# PCI_short_card_universal_-_32_BIT-3.net
KiCad netlist of a schematic drawn in Altium Designer
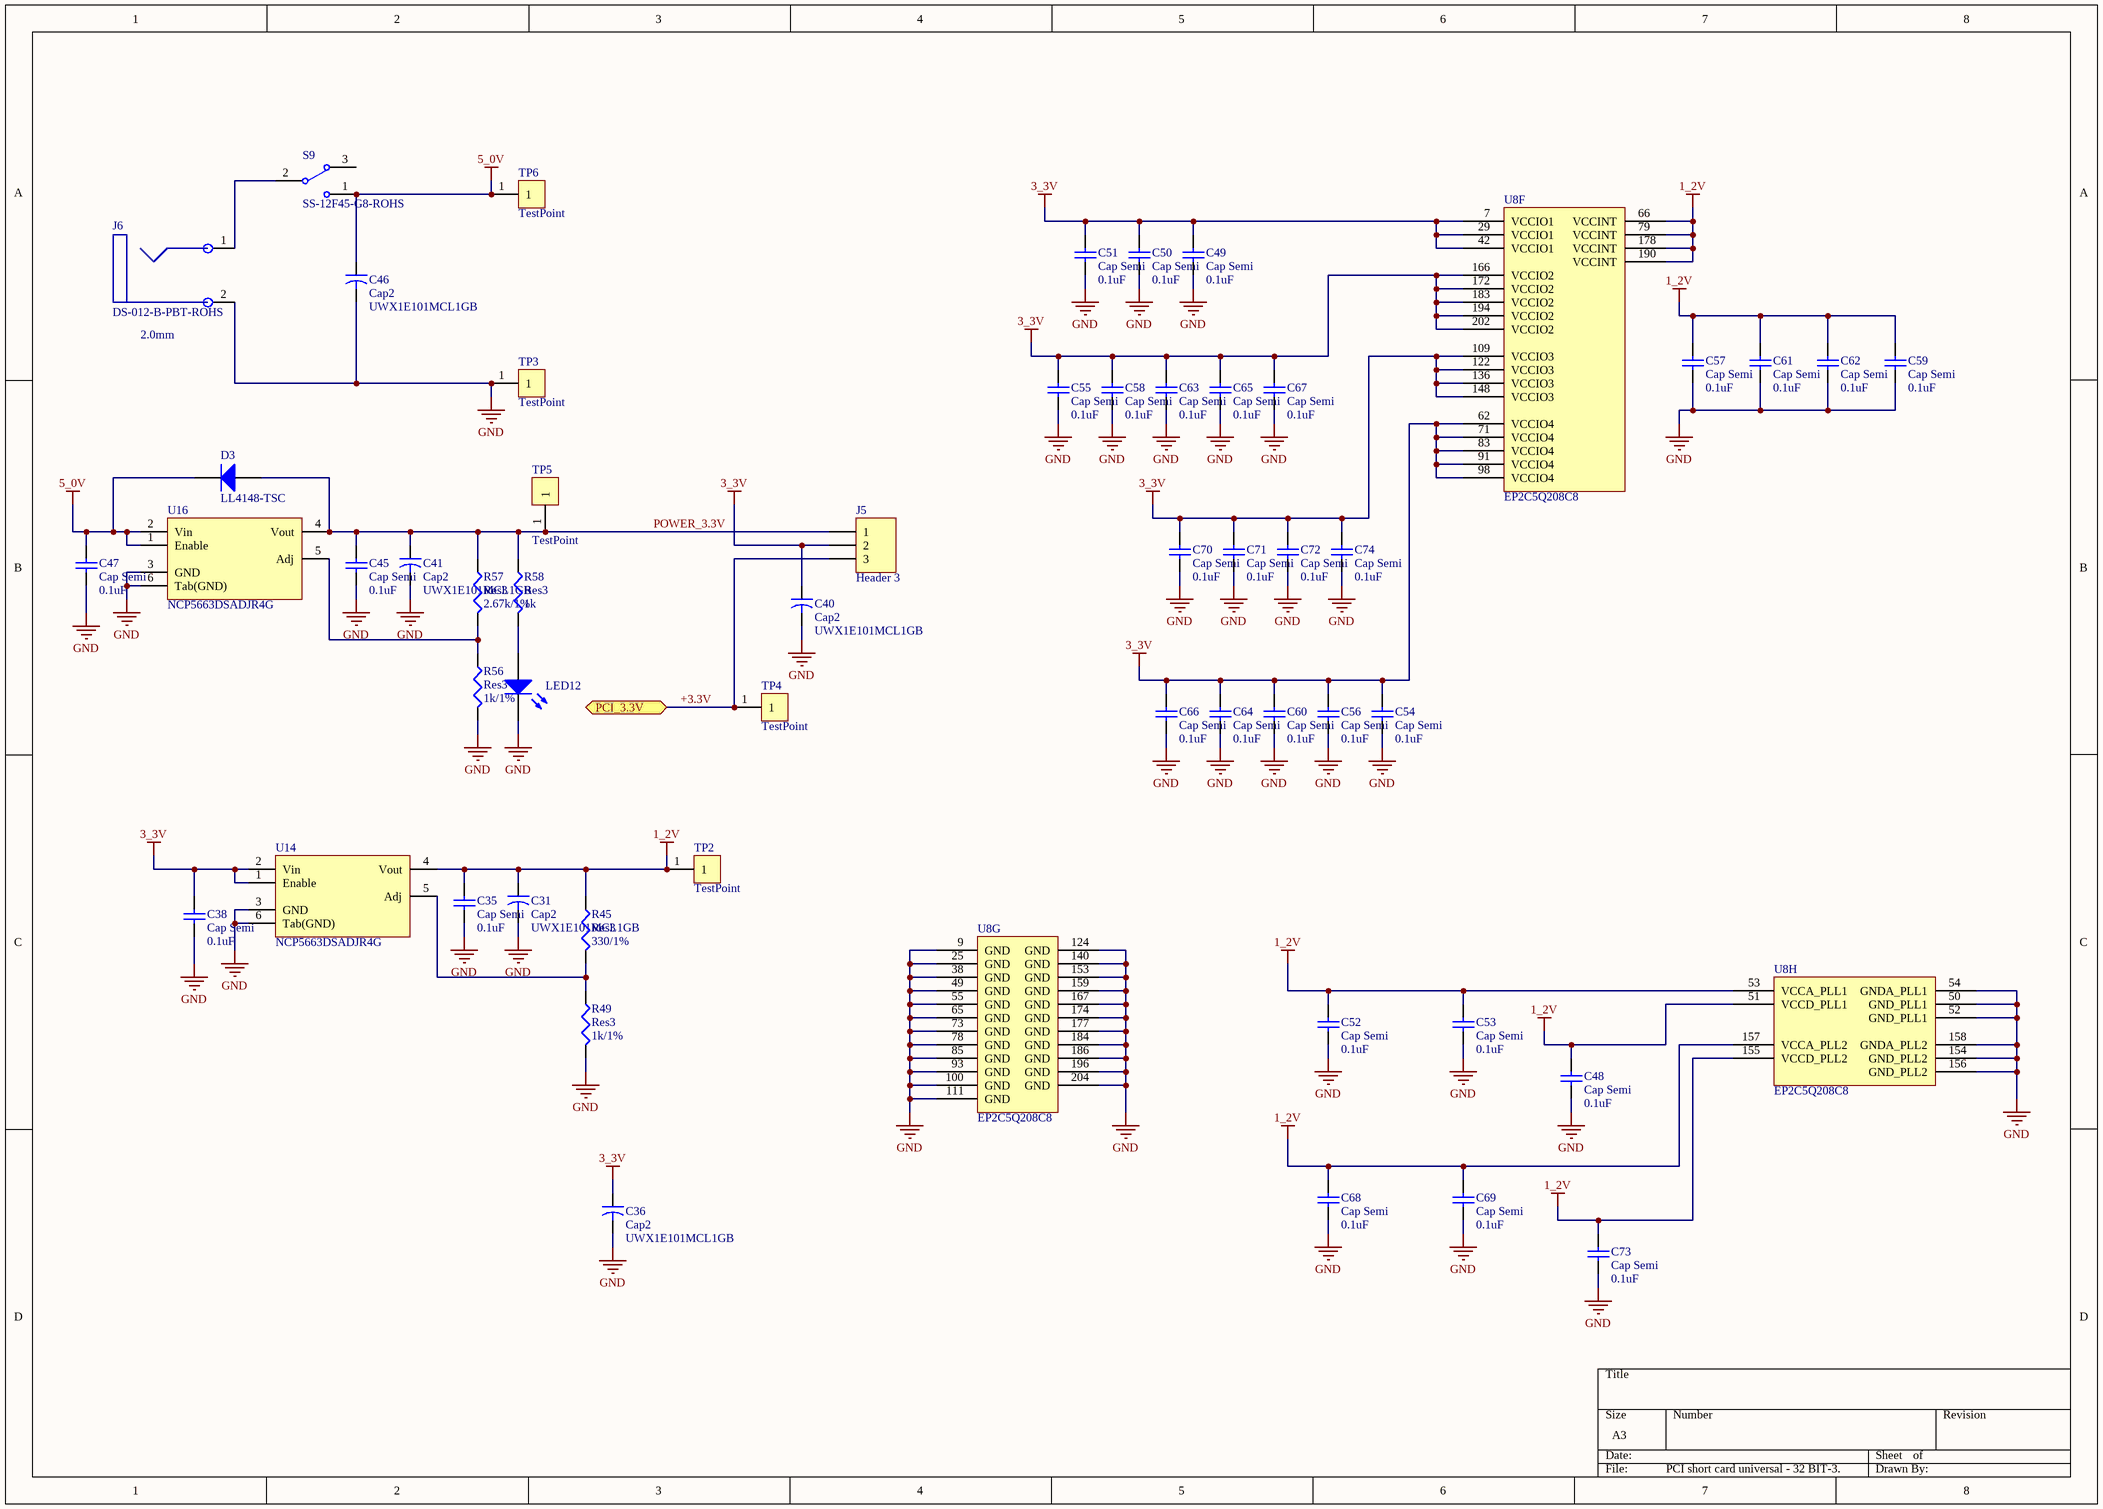
[diagram p0: PCI short card universal - 32 BIT-3.schdoc]

(export (version "E")
  (design (tool "Eeschema 10.0.6"))
  (components
    (comp (ref "C31")
      (value "Cap2")
      (footprint "ECEL_D8")
      (description "NICHICON")
      (fields (field (name "ALTIUM_VALUE") "UWX1E101MCL1GB") (field (name "PUBLISHER") "Altium Limited"))
      (libsource (lib "Miscellaneous Devices") (part "Cap2"))
    )
    (comp (ref "C35")
      (value "Cap Semi")
      (footprint "RESC1608N")
      (description "Capacitor (Semiconductor SIM Model)")
      (fields (field (name "ALTIUM_VALUE") "0.1uF") (field (name "PUBLISHER") "Altium Limited"))
      (libsource (lib "Miscellaneous Devices") (part "Cap Semi"))
    )
    (comp (ref "C36")
      (value "Cap2")
      (footprint "ECEL_D8")
      (description "NICHICON")
      (fields (field (name "ALTIUM_VALUE") "UWX1E101MCL1GB") (field (name "PUBLISHER") "Altium Limited"))
      (libsource (lib "Miscellaneous Devices") (part "Cap2"))
    )
    (comp (ref "C38")
      (value "Cap Semi")
      (footprint "RESC1608N")
      (description "Capacitor (Semiconductor SIM Model)")
      (fields (field (name "ALTIUM_VALUE") "0.1uF") (field (name "PUBLISHER") "Altium Limited"))
      (libsource (lib "Miscellaneous Devices") (part "Cap Semi"))
    )
    (comp (ref "C40")
      (value "Cap2")
      (footprint "ECEL_D8")
      (description "NICHICON")
      (fields (field (name "ALTIUM_VALUE") "UWX1E101MCL1GB") (field (name "PUBLISHER") "Altium Limited"))
      (libsource (lib "Miscellaneous Devices") (part "Cap2"))
    )
    (comp (ref "C41")
      (value "Cap2")
      (footprint "ECEL_D8")
      (description "NICHICON")
      (fields (field (name "ALTIUM_VALUE") "UWX1E101MCL1GB") (field (name "PUBLISHER") "Altium Limited"))
      (libsource (lib "Miscellaneous Devices") (part "Cap2"))
    )
    (comp (ref "C45")
      (value "Cap Semi")
      (footprint "RESC1608N")
      (description "Capacitor (Semiconductor SIM Model)")
      (fields (field (name "ALTIUM_VALUE") "0.1uF") (field (name "PUBLISHER") "Altium Limited"))
      (libsource (lib "Miscellaneous Devices") (part "Cap Semi"))
    )
    (comp (ref "C46")
      (value "Cap2")
      (footprint "ECEL_D8")
      (description "NICHICON")
      (fields (field (name "ALTIUM_VALUE") "UWX1E101MCL1GB") (field (name "PUBLISHER") "Altium Limited"))
      (libsource (lib "Miscellaneous Devices") (part "Cap2"))
    )
    (comp (ref "C47")
      (value "Cap Semi")
      (footprint "RESC1608N")
      (description "Capacitor (Semiconductor SIM Model)")
      (fields (field (name "ALTIUM_VALUE") "0.1uF") (field (name "PUBLISHER") "Altium Limited"))
      (libsource (lib "Miscellaneous Devices") (part "Cap Semi"))
    )
    (comp (ref "C48")
      (value "Cap Semi")
      (footprint "RESC1608N")
      (description "Capacitor (Semiconductor SIM Model)")
      (fields (field (name "ALTIUM_VALUE") "0.1uF") (field (name "PUBLISHER") "Altium Limited"))
      (libsource (lib "Miscellaneous Devices") (part "Cap Semi"))
    )
    (comp (ref "C49")
      (value "Cap Semi")
      (footprint "RESC1608N")
      (description "Capacitor (Semiconductor SIM Model)")
      (fields (field (name "ALTIUM_VALUE") "0.1uF") (field (name "PUBLISHER") "Altium Limited"))
      (libsource (lib "Miscellaneous Devices") (part "Cap Semi"))
    )
    (comp (ref "C50")
      (value "Cap Semi")
      (footprint "RESC1608N")
      (description "Capacitor (Semiconductor SIM Model)")
      (fields (field (name "ALTIUM_VALUE") "0.1uF") (field (name "PUBLISHER") "Altium Limited"))
      (libsource (lib "Miscellaneous Devices") (part "Cap Semi"))
    )
    (comp (ref "C51")
      (value "Cap Semi")
      (footprint "RESC1608N")
      (description "Capacitor (Semiconductor SIM Model)")
      (fields (field (name "ALTIUM_VALUE") "0.1uF") (field (name "PUBLISHER") "Altium Limited"))
      (libsource (lib "Miscellaneous Devices") (part "Cap Semi"))
    )
    (comp (ref "C52")
      (value "Cap Semi")
      (footprint "RESC1608N")
      (description "Capacitor (Semiconductor SIM Model)")
      (fields (field (name "ALTIUM_VALUE") "0.1uF") (field (name "PUBLISHER") "Altium Limited"))
      (libsource (lib "Miscellaneous Devices") (part "Cap Semi"))
    )
    (comp (ref "C53")
      (value "Cap Semi")
      (footprint "RESC1608N")
      (description "Capacitor (Semiconductor SIM Model)")
      (fields (field (name "ALTIUM_VALUE") "0.1uF") (field (name "PUBLISHER") "Altium Limited"))
      (libsource (lib "Miscellaneous Devices") (part "Cap Semi"))
    )
    (comp (ref "C54")
      (value "Cap Semi")
      (footprint "RESC1608N")
      (description "Capacitor (Semiconductor SIM Model)")
      (fields (field (name "ALTIUM_VALUE") "0.1uF") (field (name "PUBLISHER") "Altium Limited"))
      (libsource (lib "Miscellaneous Devices") (part "Cap Semi"))
    )
    (comp (ref "C55")
      (value "Cap Semi")
      (footprint "RESC1608N")
      (description "Capacitor (Semiconductor SIM Model)")
      (fields (field (name "ALTIUM_VALUE") "0.1uF") (field (name "PUBLISHER") "Altium Limited"))
      (libsource (lib "Miscellaneous Devices") (part "Cap Semi"))
    )
    (comp (ref "C56")
      (value "Cap Semi")
      (footprint "RESC1608N")
      (description "Capacitor (Semiconductor SIM Model)")
      (fields (field (name "ALTIUM_VALUE") "0.1uF") (field (name "PUBLISHER") "Altium Limited"))
      (libsource (lib "Miscellaneous Devices") (part "Cap Semi"))
    )
    (comp (ref "C57")
      (value "Cap Semi")
      (footprint "RESC1608N")
      (description "Capacitor (Semiconductor SIM Model)")
      (fields (field (name "ALTIUM_VALUE") "0.1uF") (field (name "PUBLISHER") "Altium Limited"))
      (libsource (lib "Miscellaneous Devices") (part "Cap Semi"))
    )
    (comp (ref "C58")
      (value "Cap Semi")
      (footprint "RESC1608N")
      (description "Capacitor (Semiconductor SIM Model)")
      (fields (field (name "ALTIUM_VALUE") "0.1uF") (field (name "PUBLISHER") "Altium Limited"))
      (libsource (lib "Miscellaneous Devices") (part "Cap Semi"))
    )
    (comp (ref "C59")
      (value "Cap Semi")
      (footprint "RESC1608N")
      (description "Capacitor (Semiconductor SIM Model)")
      (fields (field (name "ALTIUM_VALUE") "0.1uF") (field (name "PUBLISHER") "Altium Limited"))
      (libsource (lib "Miscellaneous Devices") (part "Cap Semi"))
    )
    (comp (ref "C60")
      (value "Cap Semi")
      (footprint "RESC1608N")
      (description "Capacitor (Semiconductor SIM Model)")
      (fields (field (name "ALTIUM_VALUE") "0.1uF") (field (name "PUBLISHER") "Altium Limited"))
      (libsource (lib "Miscellaneous Devices") (part "Cap Semi"))
    )
    (comp (ref "C61")
      (value "Cap Semi")
      (footprint "RESC1608N")
      (description "Capacitor (Semiconductor SIM Model)")
      (fields (field (name "ALTIUM_VALUE") "0.1uF") (field (name "PUBLISHER") "Altium Limited"))
      (libsource (lib "Miscellaneous Devices") (part "Cap Semi"))
    )
    (comp (ref "C62")
      (value "Cap Semi")
      (footprint "RESC1608N")
      (description "Capacitor (Semiconductor SIM Model)")
      (fields (field (name "ALTIUM_VALUE") "0.1uF") (field (name "PUBLISHER") "Altium Limited"))
      (libsource (lib "Miscellaneous Devices") (part "Cap Semi"))
    )
    (comp (ref "C63")
      (value "Cap Semi")
      (footprint "RESC1608N")
      (description "Capacitor (Semiconductor SIM Model)")
      (fields (field (name "ALTIUM_VALUE") "0.1uF") (field (name "PUBLISHER") "Altium Limited"))
      (libsource (lib "Miscellaneous Devices") (part "Cap Semi"))
    )
    (comp (ref "C64")
      (value "Cap Semi")
      (footprint "RESC1608N")
      (description "Capacitor (Semiconductor SIM Model)")
      (fields (field (name "ALTIUM_VALUE") "0.1uF") (field (name "PUBLISHER") "Altium Limited"))
      (libsource (lib "Miscellaneous Devices") (part "Cap Semi"))
    )
    (comp (ref "C65")
      (value "Cap Semi")
      (footprint "RESC1608N")
      (description "Capacitor (Semiconductor SIM Model)")
      (fields (field (name "ALTIUM_VALUE") "0.1uF") (field (name "PUBLISHER") "Altium Limited"))
      (libsource (lib "Miscellaneous Devices") (part "Cap Semi"))
    )
    (comp (ref "C66")
      (value "Cap Semi")
      (footprint "RESC1608N")
      (description "Capacitor (Semiconductor SIM Model)")
      (fields (field (name "ALTIUM_VALUE") "0.1uF") (field (name "PUBLISHER") "Altium Limited"))
      (libsource (lib "Miscellaneous Devices") (part "Cap Semi"))
    )
    (comp (ref "C67")
      (value "Cap Semi")
      (footprint "RESC1608N")
      (description "Capacitor (Semiconductor SIM Model)")
      (fields (field (name "ALTIUM_VALUE") "0.1uF") (field (name "PUBLISHER") "Altium Limited"))
      (libsource (lib "Miscellaneous Devices") (part "Cap Semi"))
    )
    (comp (ref "C68")
      (value "Cap Semi")
      (footprint "RESC1608N")
      (description "Capacitor (Semiconductor SIM Model)")
      (fields (field (name "ALTIUM_VALUE") "0.1uF") (field (name "PUBLISHER") "Altium Limited"))
      (libsource (lib "Miscellaneous Devices") (part "Cap Semi"))
    )
    (comp (ref "C69")
      (value "Cap Semi")
      (footprint "RESC1608N")
      (description "Capacitor (Semiconductor SIM Model)")
      (fields (field (name "ALTIUM_VALUE") "0.1uF") (field (name "PUBLISHER") "Altium Limited"))
      (libsource (lib "Miscellaneous Devices") (part "Cap Semi"))
    )
    (comp (ref "C70")
      (value "Cap Semi")
      (footprint "RESC1608N")
      (description "Capacitor (Semiconductor SIM Model)")
      (fields (field (name "ALTIUM_VALUE") "0.1uF") (field (name "PUBLISHER") "Altium Limited"))
      (libsource (lib "Miscellaneous Devices") (part "Cap Semi"))
    )
    (comp (ref "C71")
      (value "Cap Semi")
      (footprint "RESC1608N")
      (description "Capacitor (Semiconductor SIM Model)")
      (fields (field (name "ALTIUM_VALUE") "0.1uF") (field (name "PUBLISHER") "Altium Limited"))
      (libsource (lib "Miscellaneous Devices") (part "Cap Semi"))
    )
    (comp (ref "C72")
      (value "Cap Semi")
      (footprint "RESC1608N")
      (description "Capacitor (Semiconductor SIM Model)")
      (fields (field (name "ALTIUM_VALUE") "0.1uF") (field (name "PUBLISHER") "Altium Limited"))
      (libsource (lib "Miscellaneous Devices") (part "Cap Semi"))
    )
    (comp (ref "C73")
      (value "Cap Semi")
      (footprint "RESC1608N")
      (description "Capacitor (Semiconductor SIM Model)")
      (fields (field (name "ALTIUM_VALUE") "0.1uF") (field (name "PUBLISHER") "Altium Limited"))
      (libsource (lib "Miscellaneous Devices") (part "Cap Semi"))
    )
    (comp (ref "C74")
      (value "Cap Semi")
      (footprint "RESC1608N")
      (description "Capacitor (Semiconductor SIM Model)")
      (fields (field (name "ALTIUM_VALUE") "0.1uF") (field (name "PUBLISHER") "Altium Limited"))
      (libsource (lib "Miscellaneous Devices") (part "Cap Semi"))
    )
    (comp (ref "D3")
      (value "LL4148-TSC")
      (footprint "SOD80C")
      (description "TAIWAN SEMICONDUCTOR")
      (fields (field (name "PUBLISHER") "Altium Limited"))
      (libsource (lib "Philips Discrete Diode - Switching") (part "BAS32L"))
    )
    (comp (ref "J5")
      (value "Header 3")
      (footprint "HDR1X3")
      (description "Header, 3-Pin")
      (fields (field (name "PUBLISHER") "Altium Limited"))
      (libsource (lib "Miscellaneous Connectors") (part "Header 3"))
    )
    (comp (ref "J6")
      (value "DS-012-B-PBT-ROHS")
      (footprint "JACK")
      (description "WEALTH METAL")
      (libsource (lib "Schlib1") (part "JACK2.5mm"))
    )
    (comp (ref "LED12")
      (value "LED2")
      (footprint "LED3.2X1.6X1.1")
      (description "OASISTEK (TO-3216BC-MAE)")
      (fields (field (name "PUBLISHER") "Altium Limited"))
      (libsource (lib "Miscellaneous Devices") (part "LED2"))
    )
    (comp (ref "R45")
      (value "Res3")
      (footprint "RESC1608N")
      (description "Resistor")
      (fields (field (name "ALTIUM_VALUE") "330/1%") (field (name "PUBLISHER") "Altium Limited"))
      (libsource (lib "Miscellaneous Devices") (part "Res3"))
    )
    (comp (ref "R49")
      (value "Res3")
      (footprint "RESC1608N")
      (description "Resistor")
      (fields (field (name "ALTIUM_VALUE") "1k/1%") (field (name "PUBLISHER") "Altium Limited"))
      (libsource (lib "Miscellaneous Devices") (part "Res3"))
    )
    (comp (ref "R56")
      (value "Res3")
      (footprint "RESC1608N")
      (description "Resistor")
      (fields (field (name "ALTIUM_VALUE") "1k/1%") (field (name "PUBLISHER") "Altium Limited"))
      (libsource (lib "Miscellaneous Devices") (part "Res3"))
    )
    (comp (ref "R57")
      (value "Res3")
      (footprint "RESC1608N")
      (description "Resistor")
      (fields (field (name "ALTIUM_VALUE") "2.67k/1%") (field (name "PUBLISHER") "Altium Limited"))
      (libsource (lib "Miscellaneous Devices") (part "Res3"))
    )
    (comp (ref "R58")
      (value "Res3")
      (footprint "RESC1608N")
      (description "Resistor")
      (fields (field (name "ALTIUM_VALUE") "1k") (field (name "PUBLISHER") "Altium Limited"))
      (libsource (lib "Miscellaneous Devices") (part "Res3"))
    )
    (comp (ref "S9")
      (value "SS-12F45-G8-ROHS")
      (footprint "SLIDE_SW_2TYPE")
      (description "WEALTH METAL")
      (fields (field (name "PUBLISHER") "Altium Limited"))
      (libsource (lib "Miscellaneous Devices") (part "SW-SPDT"))
    )
    (comp (ref "TP2") (value "TestPoint") (footprint "HDR1X1") (libsource (lib "Schlib1") (part "TestPoint")))
    (comp (ref "TP3") (value "TestPoint") (footprint "HDR1X1") (libsource (lib "Schlib1") (part "TestPoint")))
    (comp (ref "TP4") (value "TestPoint") (footprint "HDR1X1") (libsource (lib "Schlib1") (part "TestPoint")))
    (comp (ref "TP5") (value "TestPoint") (footprint "HDR1X1") (libsource (lib "") (part "TestPoint_1")))
    (comp (ref "TP6") (value "TestPoint") (footprint "HDR1X1") (libsource (lib "Schlib1") (part "TestPoint")))
    (comp (ref "U8")
      (value "EP2C5Q208C8")
      (footprint "PQFP208_N")
      (fields (field (name "PUBLISHER") "Altium Limited"))
      (libsource (lib "Altera Cyclone II") (part "EP2C5Q208C8"))
    )
    (comp (ref "U14")
      (value "NCP5663DSADJR4G")
      (footprint "D2PAK(936AA)")
      (description "ON SEMI")
      (libsource (lib "Schlib1") (part "NCP5663DSADJR4G"))
    )
    (comp (ref "U16")
      (value "NCP5663DSADJR4G")
      (footprint "D2PAK(936AA)")
      (description "ON SEMI")
      (libsource (lib "Schlib1") (part "NCP5663DSADJR4G"))
    )
  )
  (nets
    (net (code "1") (name "/+3.3V") (class "Default")
      (node (ref "J5") (pin "3") (pinfunction "3_3") (pintype "passive"))
      (node (ref "TP4") (pin "1") (pinfunction "1_1") (pintype "passive"))
    )
    (net (code "2") (name "/POWER_3.3V") (class "Default")
      (node (ref "C41") (pin "1") (pinfunction "1_1") (pintype "passive"))
      (node (ref "C45") (pin "2") (pinfunction "2_2") (pintype "passive"))
      (node (ref "D3") (pin "1") (pinfunction "A_1") (pintype "passive"))
      (node (ref "J5") (pin "1") (pinfunction "1_1") (pintype "passive"))
      (node (ref "R57") (pin "1") (pinfunction "1_1") (pintype "passive"))
      (node (ref "R58") (pin "1") (pinfunction "1_1") (pintype "passive"))
      (node (ref "TP5") (pin "1") (pinfunction "1_1") (pintype "passive"))
      (node (ref "U16") (pin "4") (pinfunction "Vout_4") (pintype "passive"))
    )
    (net (code "3") (name "1_2V") (class "Default")
      (node (ref "C31") (pin "1") (pinfunction "1_1") (pintype "passive"))
      (node (ref "C35") (pin "2") (pinfunction "2_2") (pintype "passive"))
      (node (ref "C48") (pin "2") (pinfunction "2_2") (pintype "passive"))
      (node (ref "C52") (pin "2") (pinfunction "2_2") (pintype "passive"))
      (node (ref "C53") (pin "2") (pinfunction "2_2") (pintype "passive"))
      (node (ref "C57") (pin "2") (pinfunction "2_2") (pintype "passive"))
      (node (ref "C59") (pin "2") (pinfunction "2_2") (pintype "passive"))
      (node (ref "C61") (pin "2") (pinfunction "2_2") (pintype "passive"))
      (node (ref "C62") (pin "2") (pinfunction "2_2") (pintype "passive"))
      (node (ref "C68") (pin "2") (pinfunction "2_2") (pintype "passive"))
      (node (ref "C69") (pin "2") (pinfunction "2_2") (pintype "passive"))
      (node (ref "C73") (pin "2") (pinfunction "2_2") (pintype "passive"))
      (node (ref "R45") (pin "1") (pinfunction "1_1") (pintype "passive"))
      (node (ref "TP2") (pin "1") (pinfunction "1_1") (pintype "passive"))
      (node (ref "U14") (pin "4") (pinfunction "Vout_4") (pintype "passive"))
      (node (ref "U8") (pin "155") (pinfunction "VCCD_PLL2_155") (pintype "power_in"))
      (node (ref "U8") (pin "157") (pinfunction "VCCA_PLL2_157") (pintype "power_in"))
      (node (ref "U8") (pin "178") (pinfunction "VCCINT_178") (pintype "power_in"))
      (node (ref "U8") (pin "190") (pinfunction "VCCINT_190") (pintype "power_in"))
      (node (ref "U8") (pin "51") (pinfunction "VCCD_PLL1_51") (pintype "power_in"))
      (node (ref "U8") (pin "53") (pinfunction "VCCA_PLL1_53") (pintype "power_in"))
      (node (ref "U8") (pin "66") (pinfunction "VCCINT_66") (pintype "power_in"))
      (node (ref "U8") (pin "79") (pinfunction "VCCINT_79") (pintype "power_in"))
    )
    (net (code "4") (name "3_3V") (class "Default")
      (node (ref "C36") (pin "1") (pinfunction "1_1") (pintype "passive"))
      (node (ref "C38") (pin "2") (pinfunction "2_2") (pintype "passive"))
      (node (ref "C40") (pin "1") (pinfunction "1_1") (pintype "passive"))
      (node (ref "C49") (pin "2") (pinfunction "2_2") (pintype "passive"))
      (node (ref "C50") (pin "2") (pinfunction "2_2") (pintype "passive"))
      (node (ref "C51") (pin "2") (pinfunction "2_2") (pintype "passive"))
      (node (ref "C54") (pin "2") (pinfunction "2_2") (pintype "passive"))
      (node (ref "C55") (pin "2") (pinfunction "2_2") (pintype "passive"))
      (node (ref "C56") (pin "2") (pinfunction "2_2") (pintype "passive"))
      (node (ref "C58") (pin "2") (pinfunction "2_2") (pintype "passive"))
      (node (ref "C60") (pin "2") (pinfunction "2_2") (pintype "passive"))
      (node (ref "C63") (pin "2") (pinfunction "2_2") (pintype "passive"))
      (node (ref "C64") (pin "2") (pinfunction "2_2") (pintype "passive"))
      (node (ref "C65") (pin "2") (pinfunction "2_2") (pintype "passive"))
      (node (ref "C66") (pin "2") (pinfunction "2_2") (pintype "passive"))
      (node (ref "C67") (pin "2") (pinfunction "2_2") (pintype "passive"))
      (node (ref "C70") (pin "2") (pinfunction "2_2") (pintype "passive"))
      (node (ref "C71") (pin "2") (pinfunction "2_2") (pintype "passive"))
      (node (ref "C72") (pin "2") (pinfunction "2_2") (pintype "passive"))
      (node (ref "C74") (pin "2") (pinfunction "2_2") (pintype "passive"))
      (node (ref "J5") (pin "2") (pinfunction "2_2") (pintype "passive"))
      (node (ref "U14") (pin "1") (pinfunction "Enable_1") (pintype "passive"))
      (node (ref "U14") (pin "2") (pinfunction "Vin_2") (pintype "passive"))
      (node (ref "U8") (pin "109") (pinfunction "VCCIO3_109") (pintype "power_in"))
      (node (ref "U8") (pin "122") (pinfunction "VCCIO3_122") (pintype "power_in"))
      (node (ref "U8") (pin "136") (pinfunction "VCCIO3_136") (pintype "power_in"))
      (node (ref "U8") (pin "148") (pinfunction "VCCIO3_148") (pintype "power_in"))
      (node (ref "U8") (pin "166") (pinfunction "VCCIO2_166") (pintype "power_in"))
      (node (ref "U8") (pin "172") (pinfunction "VCCIO2_172") (pintype "power_in"))
      (node (ref "U8") (pin "183") (pinfunction "VCCIO2_183") (pintype "power_in"))
      (node (ref "U8") (pin "194") (pinfunction "VCCIO2_194") (pintype "power_in"))
      (node (ref "U8") (pin "202") (pinfunction "VCCIO2_202") (pintype "power_in"))
      (node (ref "U8") (pin "29") (pinfunction "VCCIO1_29") (pintype "power_in"))
      (node (ref "U8") (pin "42") (pinfunction "VCCIO1_42") (pintype "power_in"))
      (node (ref "U8") (pin "62") (pinfunction "VCCIO4_62") (pintype "power_in"))
      (node (ref "U8") (pin "7") (pinfunction "VCCIO1_7") (pintype "power_in"))
      (node (ref "U8") (pin "71") (pinfunction "VCCIO4_71") (pintype "power_in"))
      (node (ref "U8") (pin "83") (pinfunction "VCCIO4_83") (pintype "power_in"))
      (node (ref "U8") (pin "91") (pinfunction "VCCIO4_91") (pintype "power_in"))
      (node (ref "U8") (pin "98") (pinfunction "VCCIO4_98") (pintype "power_in"))
    )
    (net (code "5") (name "5_0V") (class "Default")
      (node (ref "C46") (pin "1") (pinfunction "1_1") (pintype "passive"))
      (node (ref "C47") (pin "2") (pinfunction "2_2") (pintype "passive"))
      (node (ref "D3") (pin "2") (pinfunction "K_2") (pintype "passive"))
      (node (ref "S9") (pin "1") (pinfunction "1_1") (pintype "passive"))
      (node (ref "TP6") (pin "1") (pinfunction "1_1") (pintype "passive"))
      (node (ref "U16") (pin "1") (pinfunction "Enable_1") (pintype "passive"))
      (node (ref "U16") (pin "2") (pinfunction "Vin_2") (pintype "passive"))
    )
    (net (code "6") (name "GND") (class "Default")
      (node (ref "C31") (pin "2") (pinfunction "2_2") (pintype "passive"))
      (node (ref "C35") (pin "1") (pinfunction "1_1") (pintype "passive"))
      (node (ref "C36") (pin "2") (pinfunction "2_2") (pintype "passive"))
      (node (ref "C38") (pin "1") (pinfunction "1_1") (pintype "passive"))
      (node (ref "C40") (pin "2") (pinfunction "2_2") (pintype "passive"))
      (node (ref "C41") (pin "2") (pinfunction "2_2") (pintype "passive"))
      (node (ref "C45") (pin "1") (pinfunction "1_1") (pintype "passive"))
      (node (ref "C46") (pin "2") (pinfunction "2_2") (pintype "passive"))
      (node (ref "C47") (pin "1") (pinfunction "1_1") (pintype "passive"))
      (node (ref "C48") (pin "1") (pinfunction "1_1") (pintype "passive"))
      (node (ref "C49") (pin "1") (pinfunction "1_1") (pintype "passive"))
      (node (ref "C50") (pin "1") (pinfunction "1_1") (pintype "passive"))
      (node (ref "C51") (pin "1") (pinfunction "1_1") (pintype "passive"))
      (node (ref "C52") (pin "1") (pinfunction "1_1") (pintype "passive"))
      (node (ref "C53") (pin "1") (pinfunction "1_1") (pintype "passive"))
      (node (ref "C54") (pin "1") (pinfunction "1_1") (pintype "passive"))
      (node (ref "C55") (pin "1") (pinfunction "1_1") (pintype "passive"))
      (node (ref "C56") (pin "1") (pinfunction "1_1") (pintype "passive"))
      (node (ref "C57") (pin "1") (pinfunction "1_1") (pintype "passive"))
      (node (ref "C58") (pin "1") (pinfunction "1_1") (pintype "passive"))
      (node (ref "C59") (pin "1") (pinfunction "1_1") (pintype "passive"))
      (node (ref "C60") (pin "1") (pinfunction "1_1") (pintype "passive"))
      (node (ref "C61") (pin "1") (pinfunction "1_1") (pintype "passive"))
      (node (ref "C62") (pin "1") (pinfunction "1_1") (pintype "passive"))
      (node (ref "C63") (pin "1") (pinfunction "1_1") (pintype "passive"))
      (node (ref "C64") (pin "1") (pinfunction "1_1") (pintype "passive"))
      (node (ref "C65") (pin "1") (pinfunction "1_1") (pintype "passive"))
      (node (ref "C66") (pin "1") (pinfunction "1_1") (pintype "passive"))
      (node (ref "C67") (pin "1") (pinfunction "1_1") (pintype "passive"))
      (node (ref "C68") (pin "1") (pinfunction "1_1") (pintype "passive"))
      (node (ref "C69") (pin "1") (pinfunction "1_1") (pintype "passive"))
      (node (ref "C70") (pin "1") (pinfunction "1_1") (pintype "passive"))
      (node (ref "C71") (pin "1") (pinfunction "1_1") (pintype "passive"))
      (node (ref "C72") (pin "1") (pinfunction "1_1") (pintype "passive"))
      (node (ref "C73") (pin "1") (pinfunction "1_1") (pintype "passive"))
      (node (ref "C74") (pin "1") (pinfunction "1_1") (pintype "passive"))
      (node (ref "J6") (pin "2") (pintype "passive"))
      (node (ref "LED12") (pin "2") (pinfunction "K_2") (pintype "passive"))
      (node (ref "R49") (pin "2") (pinfunction "2_2") (pintype "passive"))
      (node (ref "R56") (pin "2") (pinfunction "2_2") (pintype "passive"))
      (node (ref "TP3") (pin "1") (pinfunction "1_1") (pintype "passive"))
      (node (ref "U14") (pin "3") (pinfunction "GND_3") (pintype "passive"))
      (node (ref "U14") (pin "6") (pinfunction "Tab(GND)_6") (pintype "passive"))
      (node (ref "U16") (pin "3") (pinfunction "GND_3") (pintype "passive"))
      (node (ref "U16") (pin "6") (pinfunction "Tab(GND)_6") (pintype "passive"))
      (node (ref "U8") (pin "100") (pinfunction "GND_100") (pintype "power_in"))
      (node (ref "U8") (pin "111") (pinfunction "GND_111") (pintype "power_in"))
      (node (ref "U8") (pin "124") (pinfunction "GND_124") (pintype "power_in"))
      (node (ref "U8") (pin "140") (pinfunction "GND_140") (pintype "power_in"))
      (node (ref "U8") (pin "153") (pinfunction "GND_153") (pintype "power_in"))
      (node (ref "U8") (pin "154") (pinfunction "GND_PLL2_154") (pintype "power_in"))
      (node (ref "U8") (pin "156") (pinfunction "GND_PLL2_156") (pintype "power_in"))
      (node (ref "U8") (pin "158") (pinfunction "GNDA_PLL2_158") (pintype "power_in"))
      (node (ref "U8") (pin "159") (pinfunction "GND_159") (pintype "power_in"))
      (node (ref "U8") (pin "167") (pinfunction "GND_167") (pintype "power_in"))
      (node (ref "U8") (pin "174") (pinfunction "GND_174") (pintype "power_in"))
      (node (ref "U8") (pin "177") (pinfunction "GND_177") (pintype "power_in"))
      (node (ref "U8") (pin "184") (pinfunction "GND_184") (pintype "power_in"))
      (node (ref "U8") (pin "186") (pinfunction "GND_186") (pintype "power_in"))
      (node (ref "U8") (pin "196") (pinfunction "GND_196") (pintype "power_in"))
      (node (ref "U8") (pin "204") (pinfunction "GND_204") (pintype "power_in"))
      (node (ref "U8") (pin "25") (pinfunction "GND_25") (pintype "power_in"))
      (node (ref "U8") (pin "38") (pinfunction "GND_38") (pintype "power_in"))
      (node (ref "U8") (pin "49") (pinfunction "GND_49") (pintype "power_in"))
      (node (ref "U8") (pin "50") (pinfunction "GND_PLL1_50") (pintype "power_in"))
      (node (ref "U8") (pin "52") (pinfunction "GND_PLL1_52") (pintype "power_in"))
      (node (ref "U8") (pin "54") (pinfunction "GNDA_PLL1_54") (pintype "power_in"))
      (node (ref "U8") (pin "55") (pinfunction "GND_55") (pintype "power_in"))
      (node (ref "U8") (pin "65") (pinfunction "GND_65") (pintype "power_in"))
      (node (ref "U8") (pin "73") (pinfunction "GND_73") (pintype "power_in"))
      (node (ref "U8") (pin "78") (pinfunction "GND_78") (pintype "power_in"))
      (node (ref "U8") (pin "85") (pinfunction "GND_85") (pintype "power_in"))
      (node (ref "U8") (pin "9") (pinfunction "GND_9") (pintype "power_in"))
      (node (ref "U8") (pin "93") (pinfunction "GND_93") (pintype "power_in"))
    )
    (net (code "7") (name "Net-(J6-Pad1)") (class "Default")
      (node (ref "J6") (pin "1") (pintype "passive"))
      (node (ref "S9") (pin "2") (pinfunction "2_2") (pintype "passive"))
    )
    (net (code "8") (name "Net-(LED12-A)") (class "Default")
      (node (ref "LED12") (pin "1") (pinfunction "A_1") (pintype "passive"))
      (node (ref "R58") (pin "2") (pinfunction "2_2") (pintype "passive"))
    )
    (net (code "9") (name "Net-(U14-Adj)") (class "Default")
      (node (ref "R45") (pin "2") (pinfunction "2_2") (pintype "passive"))
      (node (ref "R49") (pin "1") (pinfunction "1_1") (pintype "passive"))
      (node (ref "U14") (pin "5") (pinfunction "Adj_5") (pintype "passive"))
    )
    (net (code "10") (name "Net-(U16-Adj)") (class "Default")
      (node (ref "R56") (pin "1") (pinfunction "1_1") (pintype "passive"))
      (node (ref "R57") (pin "2") (pinfunction "2_2") (pintype "passive"))
      (node (ref "U16") (pin "5") (pinfunction "Adj_5") (pintype "passive"))
    )
    (net (code "11") (name "unconnected-(S9-Pad3)") (class "Default")
      (node (ref "S9") (pin "3") (pinfunction "3_3") (pintype "passive"))
    )
  )
)
